# tridev.net
KiCad netlist of a schematic drawn in EAGLE
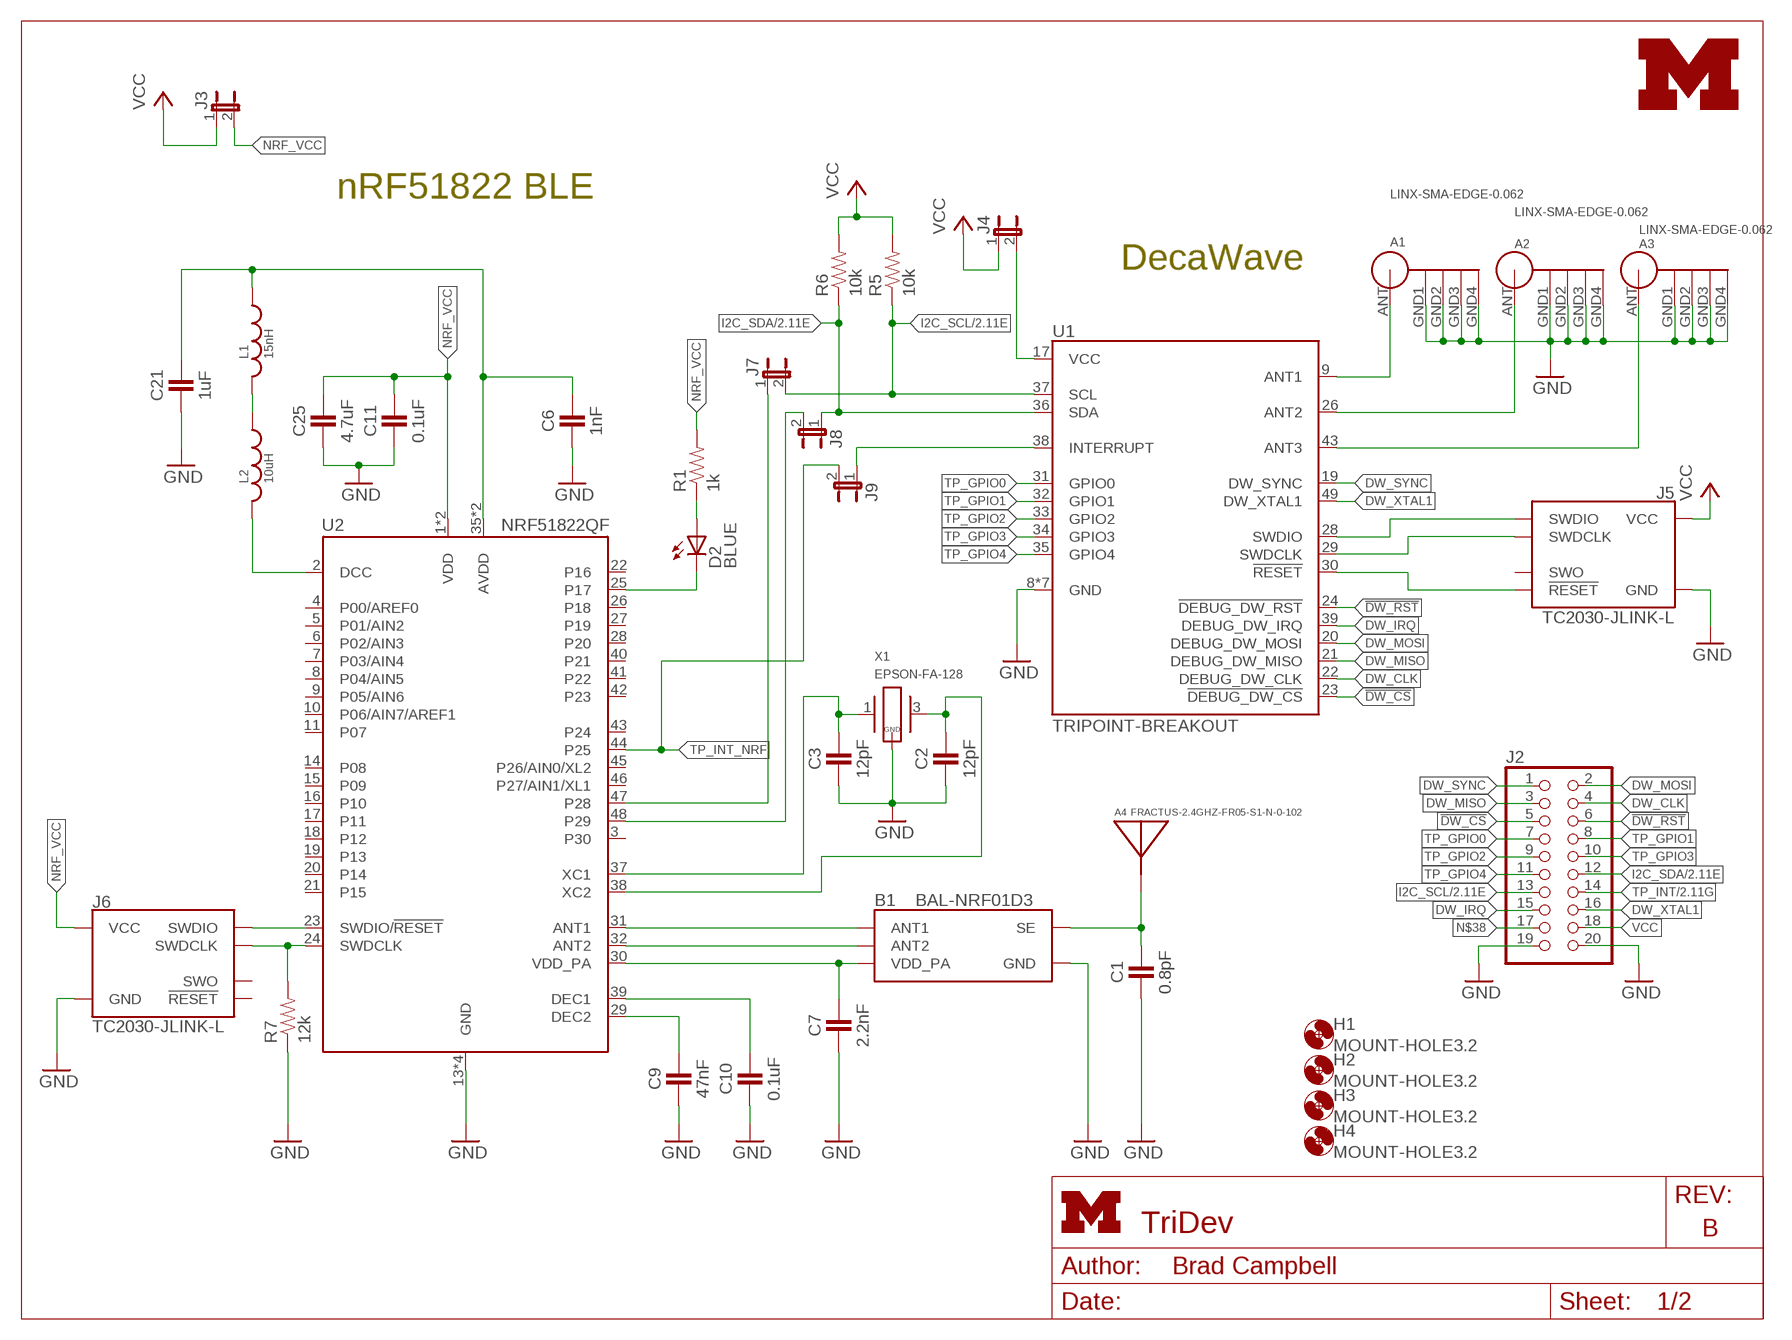
[diagram p0: schematic, sheet 1]
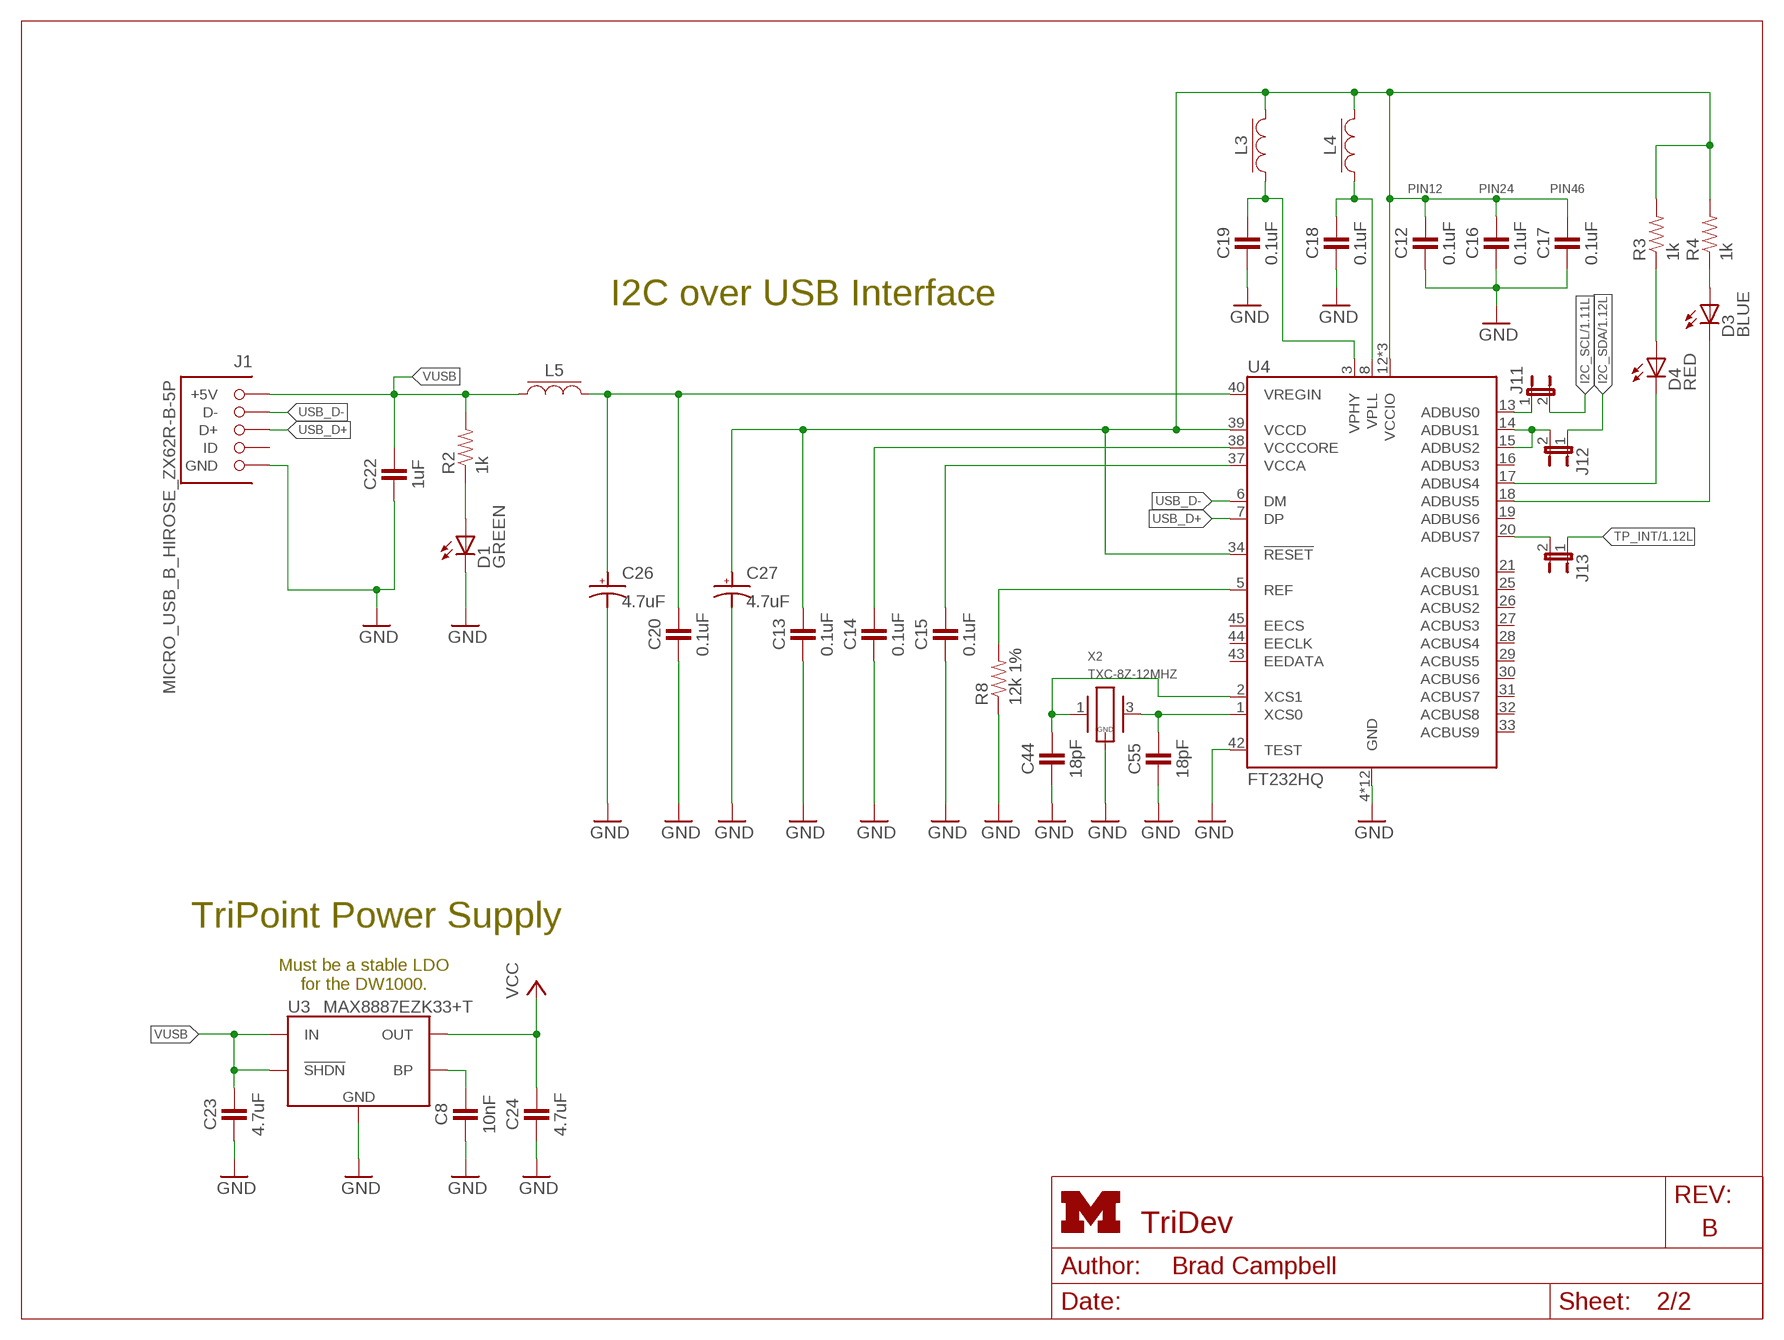
[diagram p1: schematic, sheet 2]

(export (version "E")
  (design (tool "Eeschema 10.0.6"))
  (components
    (comp (ref "A1")
      (value "LINX-SMA-EDGE-0.062")
      (footprint "eagle-import:CONSMA003.062")
      (libsource (lib "eagle-import") (part "LINX-SMA-EDGE-0.062"))
    )
    (comp (ref "A2")
      (value "LINX-SMA-EDGE-0.062")
      (footprint "eagle-import:CONSMA003.062")
      (libsource (lib "eagle-import") (part "LINX-SMA-EDGE-0.062"))
    )
    (comp (ref "A3")
      (value "LINX-SMA-EDGE-0.062")
      (footprint "eagle-import:CONSMA003.062")
      (libsource (lib "eagle-import") (part "LINX-SMA-EDGE-0.062"))
    )
    (comp (ref "A4")
      (value "FRACTUS-2.4GHZ-FR05-S1-N-0-102")
      (footprint "eagle-import:FRACTUS-ANTENNA-FR05-S1-N-0-102")
      (libsource (lib "eagle-import") (part "FRACTUS-2.4GHZ-FR05-S1-N-0-102"))
    )
    (comp (ref "B1")
      (value "BAL-NRF01D3")
      (footprint "eagle-import:BAL-NRF01D3")
      (libsource (lib "eagle-import") (part "BAL-NRF01D3"))
    )
    (comp (ref "C1")
      (value "0.8pF")
      (footprint "eagle-import:0402_CAP")
      (libsource (lib "eagle-import") (part "CAPACITOR"))
    )
    (comp (ref "C2")
      (value "12pF")
      (footprint "eagle-import:0402_CAP")
      (libsource (lib "eagle-import") (part "CAPACITOR"))
    )
    (comp (ref "C3")
      (value "12pF")
      (footprint "eagle-import:0402_CAP")
      (libsource (lib "eagle-import") (part "CAPACITOR"))
    )
    (comp (ref "C6")
      (value "1nF")
      (footprint "eagle-import:0402_CAP")
      (libsource (lib "eagle-import") (part "CAPACITOR"))
    )
    (comp (ref "C7")
      (value "2.2nF")
      (footprint "eagle-import:0402_CAP")
      (libsource (lib "eagle-import") (part "CAPACITOR"))
    )
    (comp (ref "C9")
      (value "47nF")
      (footprint "eagle-import:0402_CAP")
      (libsource (lib "eagle-import") (part "CAPACITOR"))
    )
    (comp (ref "C10")
      (value "0.1uF")
      (footprint "eagle-import:0402_CAP")
      (libsource (lib "eagle-import") (part "CAPACITOR"))
    )
    (comp (ref "C11")
      (value "0.1uF")
      (footprint "eagle-import:0402_CAP")
      (libsource (lib "eagle-import") (part "CAPACITOR"))
    )
    (comp (ref "C21")
      (value "1uF")
      (footprint "eagle-import:0402_CAP")
      (libsource (lib "eagle-import") (part "CAPACITOR"))
    )
    (comp (ref "C25")
      (value "4.7uF")
      (footprint "eagle-import:0402_CAP")
      (libsource (lib "eagle-import") (part "CAPACITOR"))
    )
    (comp (ref "D2")
      (value "BLUE")
      (footprint "eagle-import:LED-0603")
      (libsource (lib "eagle-import") (part "LED0603"))
    )
    (comp (ref "H1")
      (value "MOUNT-HOLE3.2")
      (footprint "eagle-import:3,2")
      (libsource (lib "eagle-import") (part "MOUNT-HOLE3.2"))
    )
    (comp (ref "H2")
      (value "MOUNT-HOLE3.2")
      (footprint "eagle-import:3,2")
      (libsource (lib "eagle-import") (part "MOUNT-HOLE3.2"))
    )
    (comp (ref "H3")
      (value "MOUNT-HOLE3.2")
      (footprint "eagle-import:3,2")
      (libsource (lib "eagle-import") (part "MOUNT-HOLE3.2"))
    )
    (comp (ref "H4")
      (value "MOUNT-HOLE3.2")
      (footprint "eagle-import:3,2")
      (libsource (lib "eagle-import") (part "MOUNT-HOLE3.2"))
    )
    (comp (ref "J2")
      (value "PINHD-2X10")
      (footprint "eagle-import:2X10")
      (libsource (lib "eagle-import") (part "PINHD-2X10"))
    )
    (comp (ref "J3")
      (value "JUMPER-2PTH")
      (footprint "eagle-import:1X02")
      (libsource (lib "eagle-import") (part "JUMPER-2PTH"))
    )
    (comp (ref "J4")
      (value "JUMPER-2PTH")
      (footprint "eagle-import:1X02")
      (libsource (lib "eagle-import") (part "JUMPER-2PTH"))
    )
    (comp (ref "J5")
      (value "TC2030-JLINK-L")
      (footprint "eagle-import:TC2030-IDC")
      (libsource (lib "eagle-import") (part "TC2030-JLINK-L"))
    )
    (comp (ref "J6")
      (value "TC2030-JLINK-L")
      (footprint "eagle-import:TC2030-IDC")
      (libsource (lib "eagle-import") (part "TC2030-JLINK-L"))
    )
    (comp (ref "J7")
      (value "JUMPER-2PTH")
      (footprint "eagle-import:1X02")
      (libsource (lib "eagle-import") (part "JUMPER-2PTH"))
    )
    (comp (ref "J8")
      (value "JUMPER-2PTH")
      (footprint "eagle-import:1X02")
      (libsource (lib "eagle-import") (part "JUMPER-2PTH"))
    )
    (comp (ref "J9")
      (value "JUMPER-2PTH")
      (footprint "eagle-import:1X02")
      (libsource (lib "eagle-import") (part "JUMPER-2PTH"))
    )
    (comp (ref "L1")
      (value "15nH")
      (footprint "eagle-import:0402_CAP")
      (libsource (lib "eagle-import") (part "INDUCTOR0402"))
    )
    (comp (ref "L2")
      (value "10uH")
      (footprint "eagle-import:0603_CAP")
      (libsource (lib "eagle-import") (part "INDUCTOR0603"))
    )
    (comp (ref "LOGO1")
      (value "UMICH_SOLID_SMALL")
      (footprint "eagle-import:UMICH_SOLID_75MIL")
      (libsource (lib "eagle-import") (part "UMICH_SOLID_SMALL"))
    )
    (comp (ref "R1")
      (value "1k")
      (footprint "eagle-import:0402_RES")
      (libsource (lib "eagle-import") (part "RESISTOR0402_RES"))
    )
    (comp (ref "R5")
      (value "10k")
      (footprint "eagle-import:0402_RES")
      (libsource (lib "eagle-import") (part "RESISTOR0402_RES"))
    )
    (comp (ref "R6")
      (value "10k")
      (footprint "eagle-import:0402_RES")
      (libsource (lib "eagle-import") (part "RESISTOR0402_RES"))
    )
    (comp (ref "R7")
      (value "12k")
      (footprint "eagle-import:0402_RES")
      (libsource (lib "eagle-import") (part "RESISTOR0402_RES"))
    )
    (comp (ref "U1")
      (value "TRIPOINT-BREAKOUT")
      (footprint "eagle-import:TRIPOINT-BREAKOUT")
      (libsource (lib "eagle-import") (part "TRIPOINT-BREAKOUT"))
    )
    (comp (ref "U2")
      (value "NRF51822QF")
      (footprint "eagle-import:QFN-48-6MM")
      (libsource (lib "eagle-import") (part "NRF51822QF"))
    )
    (comp (ref "X1")
      (value "EPSON-FA-128")
      (footprint "eagle-import:FA-128")
      (libsource (lib "eagle-import") (part "EPSON-FA-128"))
    )
    (comp (ref "C8")
      (value "10nF")
      (footprint "eagle-import:0402_CAP")
      (libsource (lib "eagle-import") (part "CAPACITOR"))
    )
    (comp (ref "C12")
      (value "0.1uF")
      (footprint "eagle-import:0402_CAP")
      (libsource (lib "eagle-import") (part "CAPACITOR"))
    )
    (comp (ref "C13")
      (value "0.1uF")
      (footprint "eagle-import:0402_CAP")
      (libsource (lib "eagle-import") (part "CAPACITOR"))
    )
    (comp (ref "C14")
      (value "0.1uF")
      (footprint "eagle-import:0402_CAP")
      (libsource (lib "eagle-import") (part "CAPACITOR"))
    )
    (comp (ref "C15")
      (value "0.1uF")
      (footprint "eagle-import:0402_CAP")
      (libsource (lib "eagle-import") (part "CAPACITOR"))
    )
    (comp (ref "C16")
      (value "0.1uF")
      (footprint "eagle-import:0402_CAP")
      (libsource (lib "eagle-import") (part "CAPACITOR"))
    )
    (comp (ref "C17")
      (value "0.1uF")
      (footprint "eagle-import:0402_CAP")
      (libsource (lib "eagle-import") (part "CAPACITOR"))
    )
    (comp (ref "C18")
      (value "0.1uF")
      (footprint "eagle-import:0402_CAP")
      (libsource (lib "eagle-import") (part "CAPACITOR"))
    )
    (comp (ref "C19")
      (value "0.1uF")
      (footprint "eagle-import:0402_CAP")
      (libsource (lib "eagle-import") (part "CAPACITOR"))
    )
    (comp (ref "C20")
      (value "0.1uF")
      (footprint "eagle-import:0402_CAP")
      (libsource (lib "eagle-import") (part "CAPACITOR"))
    )
    (comp (ref "C22")
      (value "1uF")
      (footprint "eagle-import:0402_CAP")
      (libsource (lib "eagle-import") (part "CAPACITOR"))
    )
    (comp (ref "C23")
      (value "4.7uF")
      (footprint "eagle-import:0402_CAP")
      (libsource (lib "eagle-import") (part "CAPACITOR"))
    )
    (comp (ref "C24")
      (value "4.7uF")
      (footprint "eagle-import:0402_CAP")
      (libsource (lib "eagle-import") (part "CAPACITOR"))
    )
    (comp (ref "C26")
      (value "4.7uF")
      (footprint "eagle-import:CAP0603")
      (libsource (lib "eagle-import") (part "CAP_POL0603"))
    )
    (comp (ref "C27")
      (value "4.7uF")
      (footprint "eagle-import:CAP0603")
      (libsource (lib "eagle-import") (part "CAP_POL0603"))
    )
    (comp (ref "C44")
      (value "18pF")
      (footprint "eagle-import:0402_CAP")
      (libsource (lib "eagle-import") (part "CAPACITOR"))
    )
    (comp (ref "C55")
      (value "18pF")
      (footprint "eagle-import:0402_CAP")
      (libsource (lib "eagle-import") (part "CAPACITOR"))
    )
    (comp (ref "D1")
      (value "GREEN")
      (footprint "eagle-import:LED-0603")
      (libsource (lib "eagle-import") (part "LED0603"))
    )
    (comp (ref "D3")
      (value "BLUE")
      (footprint "eagle-import:LED-0603")
      (libsource (lib "eagle-import") (part "LED0603"))
    )
    (comp (ref "D4")
      (value "RED")
      (footprint "eagle-import:LED-0603")
      (libsource (lib "eagle-import") (part "LED0603"))
    )
    (comp (ref "J1")
      (value "MICRO_USB_B_HIROSE_ZX62R-B-5P")
      (footprint "eagle-import:USB_MICRO_B-HIROSE-ZX62R-B-5P")
      (libsource (lib "eagle-import") (part "MICRO_USB_B_HIROSE_ZX62R-B-5P"))
    )
    (comp (ref "J11")
      (value "JUMPER-2PTH")
      (footprint "eagle-import:1X02")
      (libsource (lib "eagle-import") (part "JUMPER-2PTH"))
    )
    (comp (ref "J12")
      (value "JUMPER-2PTH")
      (footprint "eagle-import:1X02")
      (libsource (lib "eagle-import") (part "JUMPER-2PTH"))
    )
    (comp (ref "J13")
      (value "JUMPER-2PTH")
      (footprint "eagle-import:1X02")
      (libsource (lib "eagle-import") (part "JUMPER-2PTH"))
    )
    (comp (ref "L3")
      (value "FERRITE_BEAD")
      (footprint "eagle-import:0603_CAP")
      (libsource (lib "eagle-import") (part "FERRITE_BEAD"))
    )
    (comp (ref "L4")
      (value "FERRITE_BEAD")
      (footprint "eagle-import:0603_CAP")
      (libsource (lib "eagle-import") (part "FERRITE_BEAD"))
    )
    (comp (ref "L5")
      (value "FERRITE_BEAD")
      (footprint "eagle-import:0603_CAP")
      (libsource (lib "eagle-import") (part "FERRITE_BEAD"))
    )
    (comp (ref "R2")
      (value "1k")
      (footprint "eagle-import:0402_RES")
      (libsource (lib "eagle-import") (part "RESISTOR0402_RES"))
    )
    (comp (ref "R3")
      (value "1k")
      (footprint "eagle-import:0402_RES")
      (libsource (lib "eagle-import") (part "RESISTOR0402_RES"))
    )
    (comp (ref "R4")
      (value "1k")
      (footprint "eagle-import:0402_RES")
      (libsource (lib "eagle-import") (part "RESISTOR0402_RES"))
    )
    (comp (ref "R8")
      (value "12k 1%")
      (footprint "eagle-import:0402_RES")
      (libsource (lib "eagle-import") (part "RESISTOR0402_RES"))
    )
    (comp (ref "U3")
      (value "MAX8887EZK33+T")
      (footprint "eagle-import:SOT-23-5")
      (libsource (lib "eagle-import") (part "MAX8887EZK33+T"))
    )
    (comp (ref "U4")
      (value "FT232HQ")
      (footprint "eagle-import:QFN-48-8MM")
      (libsource (lib "eagle-import") (part "FT232HQ"))
    )
    (comp (ref "X2")
      (value "TXC-8Z-12MHZ")
      (footprint "eagle-import:TXC-8Z")
      (libsource (lib "eagle-import") (part "TXC-8Z-12MHZ"))
    )
  )
  (nets
    (net (code "1") (name "DW_CLK") (class "Default")
      (node (ref "J2") (pin "4") (pinfunction "4_4") (pintype "passive"))
      (node (ref "U1") (pin "22") (pinfunction "DEBUG_DW_CLK_22") (pintype "bidirectional"))
    )
    (net (code "2") (name "DW_IRQ") (class "Default")
      (node (ref "J2") (pin "15") (pinfunction "15_15") (pintype "passive"))
      (node (ref "U1") (pin "39") (pinfunction "DEBUG_DW_IRQ_39") (pintype "bidirectional"))
    )
    (net (code "3") (name "DW_MISO") (class "Default")
      (node (ref "J2") (pin "3") (pinfunction "3_3") (pintype "passive"))
      (node (ref "U1") (pin "21") (pinfunction "DEBUG_DW_MISO_21") (pintype "bidirectional"))
    )
    (net (code "4") (name "DW_MOSI") (class "Default")
      (node (ref "J2") (pin "2") (pinfunction "2_2") (pintype "passive"))
      (node (ref "U1") (pin "20") (pinfunction "DEBUG_DW_MOSI_20") (pintype "bidirectional"))
    )
    (net (code "5") (name "DW_SYNC") (class "Default")
      (node (ref "J2") (pin "1") (pinfunction "1_1") (pintype "passive"))
      (node (ref "U1") (pin "19") (pinfunction "DW_SYNC_19") (pintype "bidirectional"))
    )
    (net (code "6") (name "DW_XTAL1") (class "Default")
      (node (ref "J2") (pin "16") (pinfunction "16_16") (pintype "passive"))
      (node (ref "U1") (pin "49") (pinfunction "DW_XTAL1_49") (pintype "bidirectional"))
    )
    (net (code "7") (name "GND") (class "Default")
      (node (ref "A1") (pin "GND1") (pinfunction "P$2_GND1") (pintype "bidirectional"))
      (node (ref "A1") (pin "GND2") (pinfunction "P$3_GND2") (pintype "bidirectional"))
      (node (ref "A1") (pin "GND3") (pinfunction "P$4_GND3") (pintype "bidirectional"))
      (node (ref "A1") (pin "GND4") (pinfunction "P$5_GND4") (pintype "bidirectional"))
      (node (ref "A2") (pin "GND1") (pinfunction "P$2_GND1") (pintype "bidirectional"))
      (node (ref "A2") (pin "GND2") (pinfunction "P$3_GND2") (pintype "bidirectional"))
      (node (ref "A2") (pin "GND3") (pinfunction "P$4_GND3") (pintype "bidirectional"))
      (node (ref "A2") (pin "GND4") (pinfunction "P$5_GND4") (pintype "bidirectional"))
      (node (ref "A3") (pin "GND1") (pinfunction "P$2_GND1") (pintype "bidirectional"))
      (node (ref "A3") (pin "GND2") (pinfunction "P$3_GND2") (pintype "bidirectional"))
      (node (ref "A3") (pin "GND3") (pinfunction "P$4_GND3") (pintype "bidirectional"))
      (node (ref "A3") (pin "GND4") (pinfunction "P$5_GND4") (pintype "bidirectional"))
      (node (ref "B1") (pin "GND") (pinfunction "GND_GND") (pintype "bidirectional"))
      (node (ref "C1") (pin "2") (pinfunction "2_2") (pintype "bidirectional"))
      (node (ref "C10") (pin "2") (pinfunction "2_2") (pintype "bidirectional"))
      (node (ref "C11") (pin "2") (pinfunction "2_2") (pintype "bidirectional"))
      (node (ref "C12") (pin "2") (pinfunction "2_2") (pintype "bidirectional"))
      (node (ref "C13") (pin "2") (pinfunction "2_2") (pintype "bidirectional"))
      (node (ref "C14") (pin "2") (pinfunction "2_2") (pintype "bidirectional"))
      (node (ref "C15") (pin "2") (pinfunction "2_2") (pintype "bidirectional"))
      (node (ref "C16") (pin "2") (pinfunction "2_2") (pintype "bidirectional"))
      (node (ref "C17") (pin "2") (pinfunction "2_2") (pintype "bidirectional"))
      (node (ref "C18") (pin "2") (pinfunction "2_2") (pintype "bidirectional"))
      (node (ref "C19") (pin "2") (pinfunction "2_2") (pintype "bidirectional"))
      (node (ref "C2") (pin "2") (pinfunction "2_2") (pintype "bidirectional"))
      (node (ref "C20") (pin "2") (pinfunction "2_2") (pintype "bidirectional"))
      (node (ref "C21") (pin "2") (pinfunction "2_2") (pintype "bidirectional"))
      (node (ref "C22") (pin "2") (pinfunction "2_2") (pintype "bidirectional"))
      (node (ref "C23") (pin "2") (pinfunction "2_2") (pintype "bidirectional"))
      (node (ref "C24") (pin "2") (pinfunction "2_2") (pintype "bidirectional"))
      (node (ref "C25") (pin "2") (pinfunction "2_2") (pintype "bidirectional"))
      (node (ref "C26") (pin "NEG") (pinfunction "ANODE_NEG") (pintype "bidirectional"))
      (node (ref "C27") (pin "NEG") (pinfunction "ANODE_NEG") (pintype "bidirectional"))
      (node (ref "C3") (pin "2") (pinfunction "2_2") (pintype "bidirectional"))
      (node (ref "C44") (pin "2") (pinfunction "2_2") (pintype "bidirectional"))
      (node (ref "C55") (pin "2") (pinfunction "2_2") (pintype "bidirectional"))
      (node (ref "C6") (pin "2") (pinfunction "2_2") (pintype "bidirectional"))
      (node (ref "C7") (pin "2") (pinfunction "2_2") (pintype "bidirectional"))
      (node (ref "C8") (pin "2") (pinfunction "2_2") (pintype "bidirectional"))
      (node (ref "C9") (pin "2") (pinfunction "2_2") (pintype "bidirectional"))
      (node (ref "D1") (pin "C") (pinfunction "C_C") (pintype "passive"))
      (node (ref "J1") (pin "5") (pinfunction "GND_5") (pintype "bidirectional"))
      (node (ref "J2") (pin "19") (pinfunction "19_19") (pintype "passive"))
      (node (ref "J2") (pin "20") (pinfunction "20_20") (pintype "passive"))
      (node (ref "J5") (pin "5") (pinfunction "GND_5") (pintype "bidirectional"))
      (node (ref "J6") (pin "5") (pinfunction "GND_5") (pintype "bidirectional"))
      (node (ref "R7") (pin "1") (pinfunction "1_1") (pintype "passive"))
      (node (ref "R8") (pin "1") (pinfunction "1_1") (pintype "passive"))
      (node (ref "U1") (pin "10") (pinfunction "GND_10") (pintype "bidirectional"))
      (node (ref "U1") (pin "18") (pinfunction "GND_18") (pintype "bidirectional"))
      (node (ref "U1") (pin "25") (pinfunction "GND_25") (pintype "bidirectional"))
      (node (ref "U1") (pin "27") (pinfunction "GND_27") (pintype "bidirectional"))
      (node (ref "U1") (pin "42") (pinfunction "GND_42") (pintype "bidirectional"))
      (node (ref "U1") (pin "44") (pinfunction "GND_44") (pintype "bidirectional"))
      (node (ref "U1") (pin "8") (pinfunction "GND_8") (pintype "bidirectional"))
      (node (ref "U2") (pin "13") (pinfunction "GND_13") (pintype "bidirectional"))
      (node (ref "U2") (pin "33") (pinfunction "GND_33") (pintype "bidirectional"))
      (node (ref "U2") (pin "34") (pinfunction "GND_34") (pintype "bidirectional"))
      (node (ref "U2") (pin "GND") (pinfunction "GND_GND") (pintype "bidirectional"))
      (node (ref "U3") (pin "2") (pinfunction "GND_2") (pintype "bidirectional"))
      (node (ref "U4") (pin "10") (pinfunction "GND_10") (pintype "bidirectional"))
      (node (ref "U4") (pin "11") (pinfunction "GND_11") (pintype "bidirectional"))
      (node (ref "U4") (pin "22") (pinfunction "GND_22") (pintype "bidirectional"))
      (node (ref "U4") (pin "23") (pinfunction "GND_23") (pintype "bidirectional"))
      (node (ref "U4") (pin "35") (pinfunction "GND_35") (pintype "bidirectional"))
      (node (ref "U4") (pin "36") (pinfunction "GND_36") (pintype "bidirectional"))
      (node (ref "U4") (pin "4") (pinfunction "GND_4") (pintype "bidirectional"))
      (node (ref "U4") (pin "41") (pinfunction "GND_41") (pintype "bidirectional"))
      (node (ref "U4") (pin "42") (pinfunction "TEST_42") (pintype "bidirectional"))
      (node (ref "U4") (pin "47") (pinfunction "GND_47") (pintype "bidirectional"))
      (node (ref "U4") (pin "48") (pinfunction "GND_48") (pintype "bidirectional"))
      (node (ref "U4") (pin "9") (pinfunction "GND_9") (pintype "bidirectional"))
      (node (ref "U4") (pin "PAD") (pinfunction "GND_PAD") (pintype "bidirectional"))
      (node (ref "X1") (pin "2") (pinfunction "GND_2") (pintype "bidirectional"))
      (node (ref "X1") (pin "4") (pinfunction "GND_4") (pintype "bidirectional"))
      (node (ref "X2") (pin "2") (pinfunction "GND_2") (pintype "bidirectional"))
      (node (ref "X2") (pin "4") (pinfunction "GND_4") (pintype "bidirectional"))
    )
    (net (code "8") (name "I2C_SCL") (class "Default")
      (node (ref "J11") (pin "2") (pinfunction "2_2") (pintype "passive"))
      (node (ref "J2") (pin "13") (pinfunction "13_13") (pintype "passive"))
      (node (ref "J7") (pin "2") (pinfunction "2_2") (pintype "passive"))
      (node (ref "R5") (pin "1") (pinfunction "1_1") (pintype "passive"))
      (node (ref "U1") (pin "37") (pinfunction "SCL_37") (pintype "bidirectional"))
    )
    (net (code "9") (name "I2C_SDA") (class "Default")
      (node (ref "J12") (pin "1") (pinfunction "1_1") (pintype "passive"))
      (node (ref "J2") (pin "12") (pinfunction "12_12") (pintype "passive"))
      (node (ref "J8") (pin "1") (pinfunction "1_1") (pintype "passive"))
      (node (ref "R6") (pin "1") (pinfunction "1_1") (pintype "passive"))
      (node (ref "U1") (pin "36") (pinfunction "SDA_36") (pintype "bidirectional"))
    )
    (net (code "10") (name "N$38") (class "Default")
      (node (ref "J2") (pin "17") (pinfunction "17_17") (pintype "passive"))
    )
    (net (code "11") (name "NRF_VCC") (class "Default")
      (node (ref "C11") (pin "1") (pinfunction "1_1") (pintype "bidirectional"))
      (node (ref "C25") (pin "1") (pinfunction "1_1") (pintype "bidirectional"))
      (node (ref "J3") (pin "2") (pinfunction "2_2") (pintype "passive"))
      (node (ref "J6") (pin "1") (pinfunction "VCC_1") (pintype "bidirectional"))
      (node (ref "R1") (pin "2") (pinfunction "2_2") (pintype "passive"))
      (node (ref "U2") (pin "1") (pinfunction "VDD_1") (pintype "bidirectional"))
      (node (ref "U2") (pin "12") (pinfunction "VDD_12") (pintype "bidirectional"))
    )
    (net (code "12") (name "Net-(A4-ANTENNA)") (class "Default")
      (node (ref "A4") (pin "1") (pinfunction "ANTENNA_1") (pintype "bidirectional"))
      (node (ref "B1") (pin "SE") (pinfunction "SE_SE") (pintype "bidirectional"))
      (node (ref "C1") (pin "1") (pinfunction "1_1") (pintype "bidirectional"))
    )
    (net (code "13") (name "Net-(B1-VDD_PA)") (class "Default")
      (node (ref "B1") (pin "VCC") (pinfunction "VDD_PA_VCC") (pintype "bidirectional"))
      (node (ref "C7") (pin "1") (pinfunction "1_1") (pintype "bidirectional"))
      (node (ref "U2") (pin "30") (pinfunction "VDD_PA_30") (pintype "bidirectional"))
    )
    (net (code "14") (name "Net-(C21-Pad1)") (class "Default")
      (node (ref "C21") (pin "1") (pinfunction "1_1") (pintype "bidirectional"))
      (node (ref "C6") (pin "1") (pinfunction "1_1") (pintype "bidirectional"))
      (node (ref "L1") (pin "1") (pinfunction "1_1") (pintype "bidirectional"))
      (node (ref "U2") (pin "35") (pinfunction "AVDD_35") (pintype "bidirectional"))
      (node (ref "U2") (pin "36") (pinfunction "AVDD_36") (pintype "bidirectional"))
    )
    (net (code "15") (name "Net-(C26-CATHODE)") (class "Default")
      (node (ref "C20") (pin "1") (pinfunction "1_1") (pintype "bidirectional"))
      (node (ref "C26") (pin "POS") (pinfunction "CATHODE_POS") (pintype "bidirectional"))
      (node (ref "L5") (pin "2") (pinfunction "P$2_2") (pintype "bidirectional"))
      (node (ref "U4") (pin "40") (pinfunction "VREGIN_40") (pintype "bidirectional"))
    )
    (net (code "16") (name "Net-(C27-CATHODE)") (class "Default")
      (node (ref "C12") (pin "1") (pinfunction "1_1") (pintype "bidirectional"))
      (node (ref "C13") (pin "1") (pinfunction "1_1") (pintype "bidirectional"))
      (node (ref "C16") (pin "1") (pinfunction "1_1") (pintype "bidirectional"))
      (node (ref "C17") (pin "1") (pinfunction "1_1") (pintype "bidirectional"))
      (node (ref "C27") (pin "POS") (pinfunction "CATHODE_POS") (pintype "bidirectional"))
      (node (ref "L3") (pin "2") (pinfunction "P$2_2") (pintype "bidirectional"))
      (node (ref "L4") (pin "2") (pinfunction "P$2_2") (pintype "bidirectional"))
      (node (ref "R3") (pin "2") (pinfunction "2_2") (pintype "passive"))
      (node (ref "R4") (pin "2") (pinfunction "2_2") (pintype "passive"))
      (node (ref "U4") (pin "12") (pinfunction "VCCIO_12") (pintype "bidirectional"))
      (node (ref "U4") (pin "24") (pinfunction "VCCIO_24") (pintype "bidirectional"))
      (node (ref "U4") (pin "34") (pinfunction "~{RESET}_34") (pintype "bidirectional"))
      (node (ref "U4") (pin "39") (pinfunction "VCCD_39") (pintype "bidirectional"))
      (node (ref "U4") (pin "46") (pinfunction "VCCIO_46") (pintype "bidirectional"))
    )
    (net (code "17") (name "Net-(D1-PadA)") (class "Default")
      (node (ref "D1") (pin "A") (pinfunction "A_A") (pintype "passive"))
      (node (ref "R2") (pin "1") (pinfunction "1_1") (pintype "passive"))
    )
    (net (code "18") (name "Net-(D2-PadA)") (class "Default")
      (node (ref "D2") (pin "A") (pinfunction "A_A") (pintype "passive"))
      (node (ref "R1") (pin "1") (pinfunction "1_1") (pintype "passive"))
    )
    (net (code "19") (name "Net-(D3-PadA)") (class "Default")
      (node (ref "D3") (pin "A") (pinfunction "A_A") (pintype "passive"))
      (node (ref "R4") (pin "1") (pinfunction "1_1") (pintype "passive"))
    )
    (net (code "20") (name "Net-(D4-PadA)") (class "Default")
      (node (ref "D4") (pin "A") (pinfunction "A_A") (pintype "passive"))
      (node (ref "R3") (pin "1") (pinfunction "1_1") (pintype "passive"))
    )
    (net (code "21") (name "Net-(J5-SWDCLK)") (class "Default")
      (node (ref "J5") (pin "4") (pinfunction "SWDCLK_4") (pintype "bidirectional"))
      (node (ref "U1") (pin "29") (pinfunction "SWDCLK_29") (pintype "bidirectional"))
    )
    (net (code "22") (name "Net-(J5-SWDIO)") (class "Default")
      (node (ref "J5") (pin "2") (pinfunction "SWDIO_2") (pintype "bidirectional"))
      (node (ref "U1") (pin "28") (pinfunction "SWDIO_28") (pintype "bidirectional"))
    )
    (net (code "23") (name "Net-(J5-~{RESET})") (class "Default")
      (node (ref "J5") (pin "3") (pinfunction "~{RESET}_3") (pintype "bidirectional"))
      (node (ref "U1") (pin "30") (pinfunction "~{RESET}_30") (pintype "bidirectional"))
    )
    (net (code "24") (name "Net-(J6-SWDCLK)") (class "Default")
      (node (ref "J6") (pin "4") (pinfunction "SWDCLK_4") (pintype "bidirectional"))
      (node (ref "R7") (pin "2") (pinfunction "2_2") (pintype "passive"))
      (node (ref "U2") (pin "24") (pinfunction "SWDCLK_24") (pintype "bidirectional"))
    )
    (net (code "25") (name "Net-(J6-SWDIO)") (class "Default")
      (node (ref "J6") (pin "2") (pinfunction "SWDIO_2") (pintype "bidirectional"))
      (node (ref "U2") (pin "23") (pinfunction "SWDIO/~{RESET}_23") (pintype "bidirectional"))
    )
    (net (code "26") (name "Net-(L1-Pad2)") (class "Default")
      (node (ref "L1") (pin "2") (pinfunction "2_2") (pintype "bidirectional"))
      (node (ref "L2") (pin "1") (pinfunction "1_1") (pintype "bidirectional"))
    )
    (net (code "27") (name "Net-(L3-P$1)") (class "Default")
      (node (ref "C19") (pin "1") (pinfunction "1_1") (pintype "bidirectional"))
      (node (ref "L3") (pin "1") (pinfunction "P$1_1") (pintype "bidirectional"))
      (node (ref "U4") (pin "3") (pinfunction "VPHY_3") (pintype "bidirectional"))
    )
    (net (code "28") (name "Net-(L4-P$1)") (class "Default")
      (node (ref "C18") (pin "1") (pinfunction "1_1") (pintype "bidirectional"))
      (node (ref "L4") (pin "1") (pinfunction "P$1_1") (pintype "bidirectional"))
      (node (ref "U4") (pin "8") (pinfunction "VPLL_8") (pintype "bidirectional"))
    )
    (net (code "29") (name "Net-(U1-ANT1)") (class "Default")
      (node (ref "A1") (pin "ANT") (pinfunction "ANT_ANT") (pintype "bidirectional"))
      (node (ref "U1") (pin "9") (pinfunction "ANT1_9") (pintype "bidirectional"))
    )
    (net (code "30") (name "Net-(U1-ANT2)") (class "Default")
      (node (ref "A2") (pin "ANT") (pinfunction "ANT_ANT") (pintype "bidirectional"))
      (node (ref "U1") (pin "26") (pinfunction "ANT2_26") (pintype "bidirectional"))
    )
    (net (code "31") (name "Net-(U1-ANT3)") (class "Default")
      (node (ref "A3") (pin "ANT") (pinfunction "ANT_ANT") (pintype "bidirectional"))
      (node (ref "U1") (pin "43") (pinfunction "ANT3_43") (pintype "bidirectional"))
    )
    (net (code "32") (name "Net-(U1-VCC)") (class "Default")
      (node (ref "J4") (pin "2") (pinfunction "2_2") (pintype "passive"))
      (node (ref "U1") (pin "17") (pinfunction "VCC_17") (pintype "bidirectional"))
    )
    (net (code "33") (name "Net-(U2-ANT1)") (class "Default")
      (node (ref "B1") (pin "ANT1") (pinfunction "ANT1_ANT1") (pintype "bidirectional"))
      (node (ref "U2") (pin "31") (pinfunction "ANT1_31") (pintype "bidirectional"))
    )
    (net (code "34") (name "Net-(U2-ANT2)") (class "Default")
      (node (ref "B1") (pin "ANT2") (pinfunction "ANT2_ANT2") (pintype "bidirectional"))
      (node (ref "U2") (pin "32") (pinfunction "ANT2_32") (pintype "bidirectional"))
    )
    (net (code "35") (name "Net-(U2-DCC)") (class "Default")
      (node (ref "L2") (pin "2") (pinfunction "2_2") (pintype "bidirectional"))
      (node (ref "U2") (pin "2") (pinfunction "DCC_2") (pintype "bidirectional"))
    )
    (net (code "36") (name "Net-(U2-DEC1)") (class "Default")
      (node (ref "C10") (pin "1") (pinfunction "1_1") (pintype "bidirectional"))
      (node (ref "U2") (pin "39") (pinfunction "DEC1_39") (pintype "bidirectional"))
    )
    (net (code "37") (name "Net-(U2-DEC2)") (class "Default")
      (node (ref "C9") (pin "1") (pinfunction "1_1") (pintype "bidirectional"))
      (node (ref "U2") (pin "29") (pinfunction "DEC2_29") (pintype "bidirectional"))
    )
    (net (code "38") (name "Net-(U2-P17)") (class "Default")
      (node (ref "D2") (pin "C") (pinfunction "C_C") (pintype "passive"))
      (node (ref "U2") (pin "25") (pinfunction "P17_25") (pintype "bidirectional"))
    )
    (net (code "39") (name "Net-(U2-P28)") (class "Default")
      (node (ref "J7") (pin "1") (pinfunction "1_1") (pintype "passive"))
      (node (ref "U2") (pin "47") (pinfunction "P28_47") (pintype "bidirectional"))
    )
    (net (code "40") (name "Net-(U2-P29)") (class "Default")
      (node (ref "J8") (pin "2") (pinfunction "2_2") (pintype "passive"))
      (node (ref "U2") (pin "48") (pinfunction "P29_48") (pintype "bidirectional"))
    )
    (net (code "41") (name "Net-(U2-XC1)") (class "Default")
      (node (ref "C3") (pin "1") (pinfunction "1_1") (pintype "bidirectional"))
      (node (ref "U2") (pin "37") (pinfunction "XC1_37") (pintype "bidirectional"))
      (node (ref "X1") (pin "1") (pinfunction "1_1") (pintype "bidirectional"))
    )
    (net (code "42") (name "Net-(U2-XC2)") (class "Default")
      (node (ref "C2") (pin "1") (pinfunction "1_1") (pintype "bidirectional"))
      (node (ref "U2") (pin "38") (pinfunction "XC2_38") (pintype "bidirectional"))
      (node (ref "X1") (pin "3") (pinfunction "2_3") (pintype "bidirectional"))
    )
    (net (code "43") (name "Net-(U3-BP)") (class "Default")
      (node (ref "C8") (pin "1") (pinfunction "1_1") (pintype "bidirectional"))
      (node (ref "U3") (pin "4") (pinfunction "BP_4") (pintype "bidirectional"))
    )
    (net (code "44") (name "Net-(U4-ADBUS0)") (class "Default")
      (node (ref "J11") (pin "1") (pinfunction "1_1") (pintype "passive"))
      (node (ref "U4") (pin "13") (pinfunction "ADBUS0_13") (pintype "bidirectional"))
    )
    (net (code "45") (name "Net-(U4-ADBUS1)") (class "Default")
      (node (ref "J12") (pin "2") (pinfunction "2_2") (pintype "passive"))
      (node (ref "U4") (pin "14") (pinfunction "ADBUS1_14") (pintype "bidirectional"))
      (node (ref "U4") (pin "15") (pinfunction "ADBUS2_15") (pintype "bidirectional"))
    )
    (net (code "46") (name "Net-(U4-ADBUS4)") (class "Default")
      (node (ref "D4") (pin "C") (pinfunction "C_C") (pintype "passive"))
      (node (ref "U4") (pin "17") (pinfunction "ADBUS4_17") (pintype "bidirectional"))
    )
    (net (code "47") (name "Net-(U4-ADBUS5)") (class "Default")
      (node (ref "D3") (pin "C") (pinfunction "C_C") (pintype "passive"))
      (node (ref "U4") (pin "18") (pinfunction "ADBUS5_18") (pintype "bidirectional"))
    )
    (net (code "48") (name "Net-(U4-ADBUS7)") (class "Default")
      (node (ref "J13") (pin "2") (pinfunction "2_2") (pintype "passive"))
      (node (ref "U4") (pin "20") (pinfunction "ADBUS7_20") (pintype "bidirectional"))
    )
    (net (code "49") (name "Net-(U4-REF)") (class "Default")
      (node (ref "R8") (pin "2") (pinfunction "2_2") (pintype "passive"))
      (node (ref "U4") (pin "5") (pinfunction "REF_5") (pintype "bidirectional"))
    )
    (net (code "50") (name "Net-(U4-VCCA)") (class "Default")
      (node (ref "C15") (pin "1") (pinfunction "1_1") (pintype "bidirectional"))
      (node (ref "U4") (pin "37") (pinfunction "VCCA_37") (pintype "bidirectional"))
    )
    (net (code "51") (name "Net-(U4-VCCCORE)") (class "Default")
      (node (ref "C14") (pin "1") (pinfunction "1_1") (pintype "bidirectional"))
      (node (ref "U4") (pin "38") (pinfunction "VCCCORE_38") (pintype "bidirectional"))
    )
    (net (code "52") (name "Net-(U4-XCS0)") (class "Default")
      (node (ref "C55") (pin "1") (pinfunction "1_1") (pintype "bidirectional"))
      (node (ref "U4") (pin "1") (pinfunction "XCS0_1") (pintype "bidirectional"))
      (node (ref "X2") (pin "3") (pinfunction "2_3") (pintype "bidirectional"))
    )
    (net (code "53") (name "Net-(U4-XCS1)") (class "Default")
      (node (ref "C44") (pin "1") (pinfunction "1_1") (pintype "bidirectional"))
      (node (ref "U4") (pin "2") (pinfunction "XCS1_2") (pintype "bidirectional"))
      (node (ref "X2") (pin "1") (pinfunction "1_1") (pintype "bidirectional"))
    )
    (net (code "54") (name "TP_GPIO0") (class "Default")
      (node (ref "J2") (pin "7") (pinfunction "7_7") (pintype "passive"))
      (node (ref "U1") (pin "31") (pinfunction "GPIO0_31") (pintype "bidirectional"))
    )
    (net (code "55") (name "TP_GPIO1") (class "Default")
      (node (ref "J2") (pin "8") (pinfunction "8_8") (pintype "passive"))
      (node (ref "U1") (pin "32") (pinfunction "GPIO1_32") (pintype "bidirectional"))
    )
    (net (code "56") (name "TP_GPIO2") (class "Default")
      (node (ref "J2") (pin "9") (pinfunction "9_9") (pintype "passive"))
      (node (ref "U1") (pin "33") (pinfunction "GPIO2_33") (pintype "bidirectional"))
    )
    (net (code "57") (name "TP_GPIO3") (class "Default")
      (node (ref "J2") (pin "10") (pinfunction "10_10") (pintype "passive"))
      (node (ref "U1") (pin "34") (pinfunction "GPIO3_34") (pintype "bidirectional"))
    )
    (net (code "58") (name "TP_GPIO4") (class "Default")
      (node (ref "J2") (pin "11") (pinfunction "11_11") (pintype "passive"))
      (node (ref "U1") (pin "35") (pinfunction "GPIO4_35") (pintype "bidirectional"))
    )
    (net (code "59") (name "TP_INT") (class "Default")
      (node (ref "J13") (pin "1") (pinfunction "1_1") (pintype "passive"))
      (node (ref "J2") (pin "14") (pinfunction "14_14") (pintype "passive"))
      (node (ref "J9") (pin "1") (pinfunction "1_1") (pintype "passive"))
      (node (ref "U1") (pin "38") (pinfunction "INTERRUPT_38") (pintype "bidirectional"))
    )
    (net (code "60") (name "TP_INT_NRF") (class "Default")
      (node (ref "J9") (pin "2") (pinfunction "2_2") (pintype "passive"))
      (node (ref "U2") (pin "44") (pinfunction "P25_44") (pintype "bidirectional"))
    )
    (net (code "61") (name "USB_D+") (class "Default")
      (node (ref "J1") (pin "3") (pinfunction "D+_3") (pintype "bidirectional"))
      (node (ref "U4") (pin "7") (pinfunction "DP_7") (pintype "bidirectional"))
    )
    (net (code "62") (name "USB_D-") (class "Default")
      (node (ref "J1") (pin "2") (pinfunction "D-_2") (pintype "bidirectional"))
      (node (ref "U4") (pin "6") (pinfunction "DM_6") (pintype "bidirectional"))
    )
    (net (code "63") (name "VCC") (class "Default")
      (node (ref "C24") (pin "1") (pinfunction "1_1") (pintype "bidirectional"))
      (node (ref "J2") (pin "18") (pinfunction "18_18") (pintype "passive"))
      (node (ref "J3") (pin "1") (pinfunction "1_1") (pintype "passive"))
      (node (ref "J4") (pin "1") (pinfunction "1_1") (pintype "passive"))
      (node (ref "J5") (pin "1") (pinfunction "VCC_1") (pintype "bidirectional"))
      (node (ref "R5") (pin "2") (pinfunction "2_2") (pintype "passive"))
      (node (ref "R6") (pin "2") (pinfunction "2_2") (pintype "passive"))
      (node (ref "U3") (pin "5") (pinfunction "OUT_5") (pintype "bidirectional"))
    )
    (net (code "64") (name "VUSB") (class "Default")
      (node (ref "C22") (pin "1") (pinfunction "1_1") (pintype "bidirectional"))
      (node (ref "C23") (pin "1") (pinfunction "1_1") (pintype "bidirectional"))
      (node (ref "J1") (pin "1") (pinfunction "+5V_1") (pintype "bidirectional"))
      (node (ref "L5") (pin "1") (pinfunction "P$1_1") (pintype "bidirectional"))
      (node (ref "R2") (pin "2") (pinfunction "2_2") (pintype "passive"))
      (node (ref "U3") (pin "1") (pinfunction "IN_1") (pintype "bidirectional"))
      (node (ref "U3") (pin "3") (pinfunction "~{SHDN}_3") (pintype "bidirectional"))
    )
    (net (code "65") (name "unconnected-(J1-ID-Pad4)") (class "Default")
      (node (ref "J1") (pin "4") (pinfunction "ID_4") (pintype "bidirectional"))
    )
    (net (code "66") (name "unconnected-(J5-SWO-Pad6)") (class "Default")
      (node (ref "J5") (pin "6") (pinfunction "SWO_6") (pintype "bidirectional"))
    )
    (net (code "67") (name "unconnected-(J6-SWO-Pad6)") (class "Default")
      (node (ref "J6") (pin "6") (pinfunction "SWO_6") (pintype "bidirectional"))
    )
    (net (code "68") (name "unconnected-(J6-~{RESET}-Pad3)") (class "Default")
      (node (ref "J6") (pin "3") (pinfunction "~{RESET}_3") (pintype "bidirectional"))
    )
    (net (code "69") (name "unconnected-(U2-P00{slash}AREF0-Pad4)") (class "Default")
      (node (ref "U2") (pin "4") (pinfunction "P00/AREF0_4") (pintype "bidirectional"))
    )
    (net (code "70") (name "unconnected-(U2-P01{slash}AIN2-Pad5)") (class "Default")
      (node (ref "U2") (pin "5") (pinfunction "P01/AIN2_5") (pintype "bidirectional"))
    )
    (net (code "71") (name "unconnected-(U2-P02{slash}AIN3-Pad6)") (class "Default")
      (node (ref "U2") (pin "6") (pinfunction "P02/AIN3_6") (pintype "bidirectional"))
    )
    (net (code "72") (name "unconnected-(U2-P03{slash}AIN4-Pad7)") (class "Default")
      (node (ref "U2") (pin "7") (pinfunction "P03/AIN4_7") (pintype "bidirectional"))
    )
    (net (code "73") (name "unconnected-(U2-P04{slash}AIN5-Pad8)") (class "Default")
      (node (ref "U2") (pin "8") (pinfunction "P04/AIN5_8") (pintype "bidirectional"))
    )
    (net (code "74") (name "unconnected-(U2-P05{slash}AIN6-Pad9)") (class "Default")
      (node (ref "U2") (pin "9") (pinfunction "P05/AIN6_9") (pintype "bidirectional"))
    )
    (net (code "75") (name "unconnected-(U2-P06{slash}AIN7{slash}AREF1-Pad10)") (class "Default")
      (node (ref "U2") (pin "10") (pinfunction "P06/AIN7/AREF1_10") (pintype "bidirectional"))
    )
    (net (code "76") (name "unconnected-(U2-P07-Pad11)") (class "Default")
      (node (ref "U2") (pin "11") (pinfunction "P07_11") (pintype "bidirectional"))
    )
    (net (code "77") (name "unconnected-(U2-P08-Pad14)") (class "Default")
      (node (ref "U2") (pin "14") (pinfunction "P08_14") (pintype "bidirectional"))
    )
    (net (code "78") (name "unconnected-(U2-P09-Pad15)") (class "Default")
      (node (ref "U2") (pin "15") (pinfunction "P09_15") (pintype "bidirectional"))
    )
    (net (code "79") (name "unconnected-(U2-P10-Pad16)") (class "Default")
      (node (ref "U2") (pin "16") (pinfunction "P10_16") (pintype "bidirectional"))
    )
    (net (code "80") (name "unconnected-(U2-P11-Pad17)") (class "Default")
      (node (ref "U2") (pin "17") (pinfunction "P11_17") (pintype "bidirectional"))
    )
    (net (code "81") (name "unconnected-(U2-P12-Pad18)") (class "Default")
      (node (ref "U2") (pin "18") (pinfunction "P12_18") (pintype "bidirectional"))
    )
    (net (code "82") (name "unconnected-(U2-P13-Pad19)") (class "Default")
      (node (ref "U2") (pin "19") (pinfunction "P13_19") (pintype "bidirectional"))
    )
    (net (code "83") (name "unconnected-(U2-P14-Pad20)") (class "Default")
      (node (ref "U2") (pin "20") (pinfunction "P14_20") (pintype "bidirectional"))
    )
    (net (code "84") (name "unconnected-(U2-P15-Pad21)") (class "Default")
      (node (ref "U2") (pin "21") (pinfunction "P15_21") (pintype "bidirectional"))
    )
    (net (code "85") (name "unconnected-(U2-P16-Pad22)") (class "Default")
      (node (ref "U2") (pin "22") (pinfunction "P16_22") (pintype "bidirectional"))
    )
    (net (code "86") (name "unconnected-(U2-P18-Pad26)") (class "Default")
      (node (ref "U2") (pin "26") (pinfunction "P18_26") (pintype "bidirectional"))
    )
    (net (code "87") (name "unconnected-(U2-P19-Pad27)") (class "Default")
      (node (ref "U2") (pin "27") (pinfunction "P19_27") (pintype "bidirectional"))
    )
    (net (code "88") (name "unconnected-(U2-P20-Pad28)") (class "Default")
      (node (ref "U2") (pin "28") (pinfunction "P20_28") (pintype "bidirectional"))
    )
    (net (code "89") (name "unconnected-(U2-P21-Pad40)") (class "Default")
      (node (ref "U2") (pin "40") (pinfunction "P21_40") (pintype "bidirectional"))
    )
    (net (code "90") (name "unconnected-(U2-P22-Pad41)") (class "Default")
      (node (ref "U2") (pin "41") (pinfunction "P22_41") (pintype "bidirectional"))
    )
    (net (code "91") (name "unconnected-(U2-P23-Pad42)") (class "Default")
      (node (ref "U2") (pin "42") (pinfunction "P23_42") (pintype "bidirectional"))
    )
    (net (code "92") (name "unconnected-(U2-P24-Pad43)") (class "Default")
      (node (ref "U2") (pin "43") (pinfunction "P24_43") (pintype "bidirectional"))
    )
    (net (code "93") (name "unconnected-(U2-P26{slash}AIN0{slash}XL2-Pad45)") (class "Default")
      (node (ref "U2") (pin "45") (pinfunction "P26/AIN0/XL2_45") (pintype "bidirectional"))
    )
    (net (code "94") (name "unconnected-(U2-P27{slash}AIN1{slash}XL1-Pad46)") (class "Default")
      (node (ref "U2") (pin "46") (pinfunction "P27/AIN1/XL1_46") (pintype "bidirectional"))
    )
    (net (code "95") (name "unconnected-(U2-P30-Pad3)") (class "Default")
      (node (ref "U2") (pin "3") (pinfunction "P30_3") (pintype "bidirectional"))
    )
    (net (code "96") (name "unconnected-(U4-ACBUS0-Pad21)") (class "Default")
      (node (ref "U4") (pin "21") (pinfunction "ACBUS0_21") (pintype "bidirectional"))
    )
    (net (code "97") (name "unconnected-(U4-ACBUS1-Pad25)") (class "Default")
      (node (ref "U4") (pin "25") (pinfunction "ACBUS1_25") (pintype "bidirectional"))
    )
    (net (code "98") (name "unconnected-(U4-ACBUS2-Pad26)") (class "Default")
      (node (ref "U4") (pin "26") (pinfunction "ACBUS2_26") (pintype "bidirectional"))
    )
    (net (code "99") (name "unconnected-(U4-ACBUS3-Pad27)") (class "Default")
      (node (ref "U4") (pin "27") (pinfunction "ACBUS3_27") (pintype "bidirectional"))
    )
    (net (code "100") (name "unconnected-(U4-ACBUS4-Pad28)") (class "Default")
      (node (ref "U4") (pin "28") (pinfunction "ACBUS4_28") (pintype "bidirectional"))
    )
    (net (code "101") (name "unconnected-(U4-ACBUS5-Pad29)") (class "Default")
      (node (ref "U4") (pin "29") (pinfunction "ACBUS5_29") (pintype "bidirectional"))
    )
    (net (code "102") (name "unconnected-(U4-ACBUS6-Pad30)") (class "Default")
      (node (ref "U4") (pin "30") (pinfunction "ACBUS6_30") (pintype "bidirectional"))
    )
    (net (code "103") (name "unconnected-(U4-ACBUS7-Pad31)") (class "Default")
      (node (ref "U4") (pin "31") (pinfunction "ACBUS7_31") (pintype "bidirectional"))
    )
    (net (code "104") (name "unconnected-(U4-ACBUS8-Pad32)") (class "Default")
      (node (ref "U4") (pin "32") (pinfunction "ACBUS8_32") (pintype "bidirectional"))
    )
    (net (code "105") (name "unconnected-(U4-ACBUS9-Pad33)") (class "Default")
      (node (ref "U4") (pin "33") (pinfunction "ACBUS9_33") (pintype "bidirectional"))
    )
    (net (code "106") (name "unconnected-(U4-ADBUS3-Pad16)") (class "Default")
      (node (ref "U4") (pin "16") (pinfunction "ADBUS3_16") (pintype "bidirectional"))
    )
    (net (code "107") (name "unconnected-(U4-ADBUS6-Pad19)") (class "Default")
      (node (ref "U4") (pin "19") (pinfunction "ADBUS6_19") (pintype "bidirectional"))
    )
    (net (code "108") (name "unconnected-(U4-EECLK-Pad44)") (class "Default")
      (node (ref "U4") (pin "44") (pinfunction "EECLK_44") (pintype "bidirectional"))
    )
    (net (code "109") (name "unconnected-(U4-EECS-Pad45)") (class "Default")
      (node (ref "U4") (pin "45") (pinfunction "EECS_45") (pintype "bidirectional"))
    )
    (net (code "110") (name "unconnected-(U4-EEDATA-Pad43)") (class "Default")
      (node (ref "U4") (pin "43") (pinfunction "EEDATA_43") (pintype "bidirectional"))
    )
    (net (code "111") (name "~{DW_CS}") (class "Default")
      (node (ref "J2") (pin "5") (pinfunction "5_5") (pintype "passive"))
      (node (ref "U1") (pin "23") (pinfunction "~{DEBUG_DW_CS}_23") (pintype "bidirectional"))
    )
    (net (code "112") (name "~{DW_RST}") (class "Default")
      (node (ref "J2") (pin "6") (pinfunction "6_6") (pintype "passive"))
      (node (ref "U1") (pin "24") (pinfunction "~{DEBUG_DW_RST}_24") (pintype "bidirectional"))
    )
  )
)
